# top.net
KiCad netlist of a schematic drawn in EAGLE
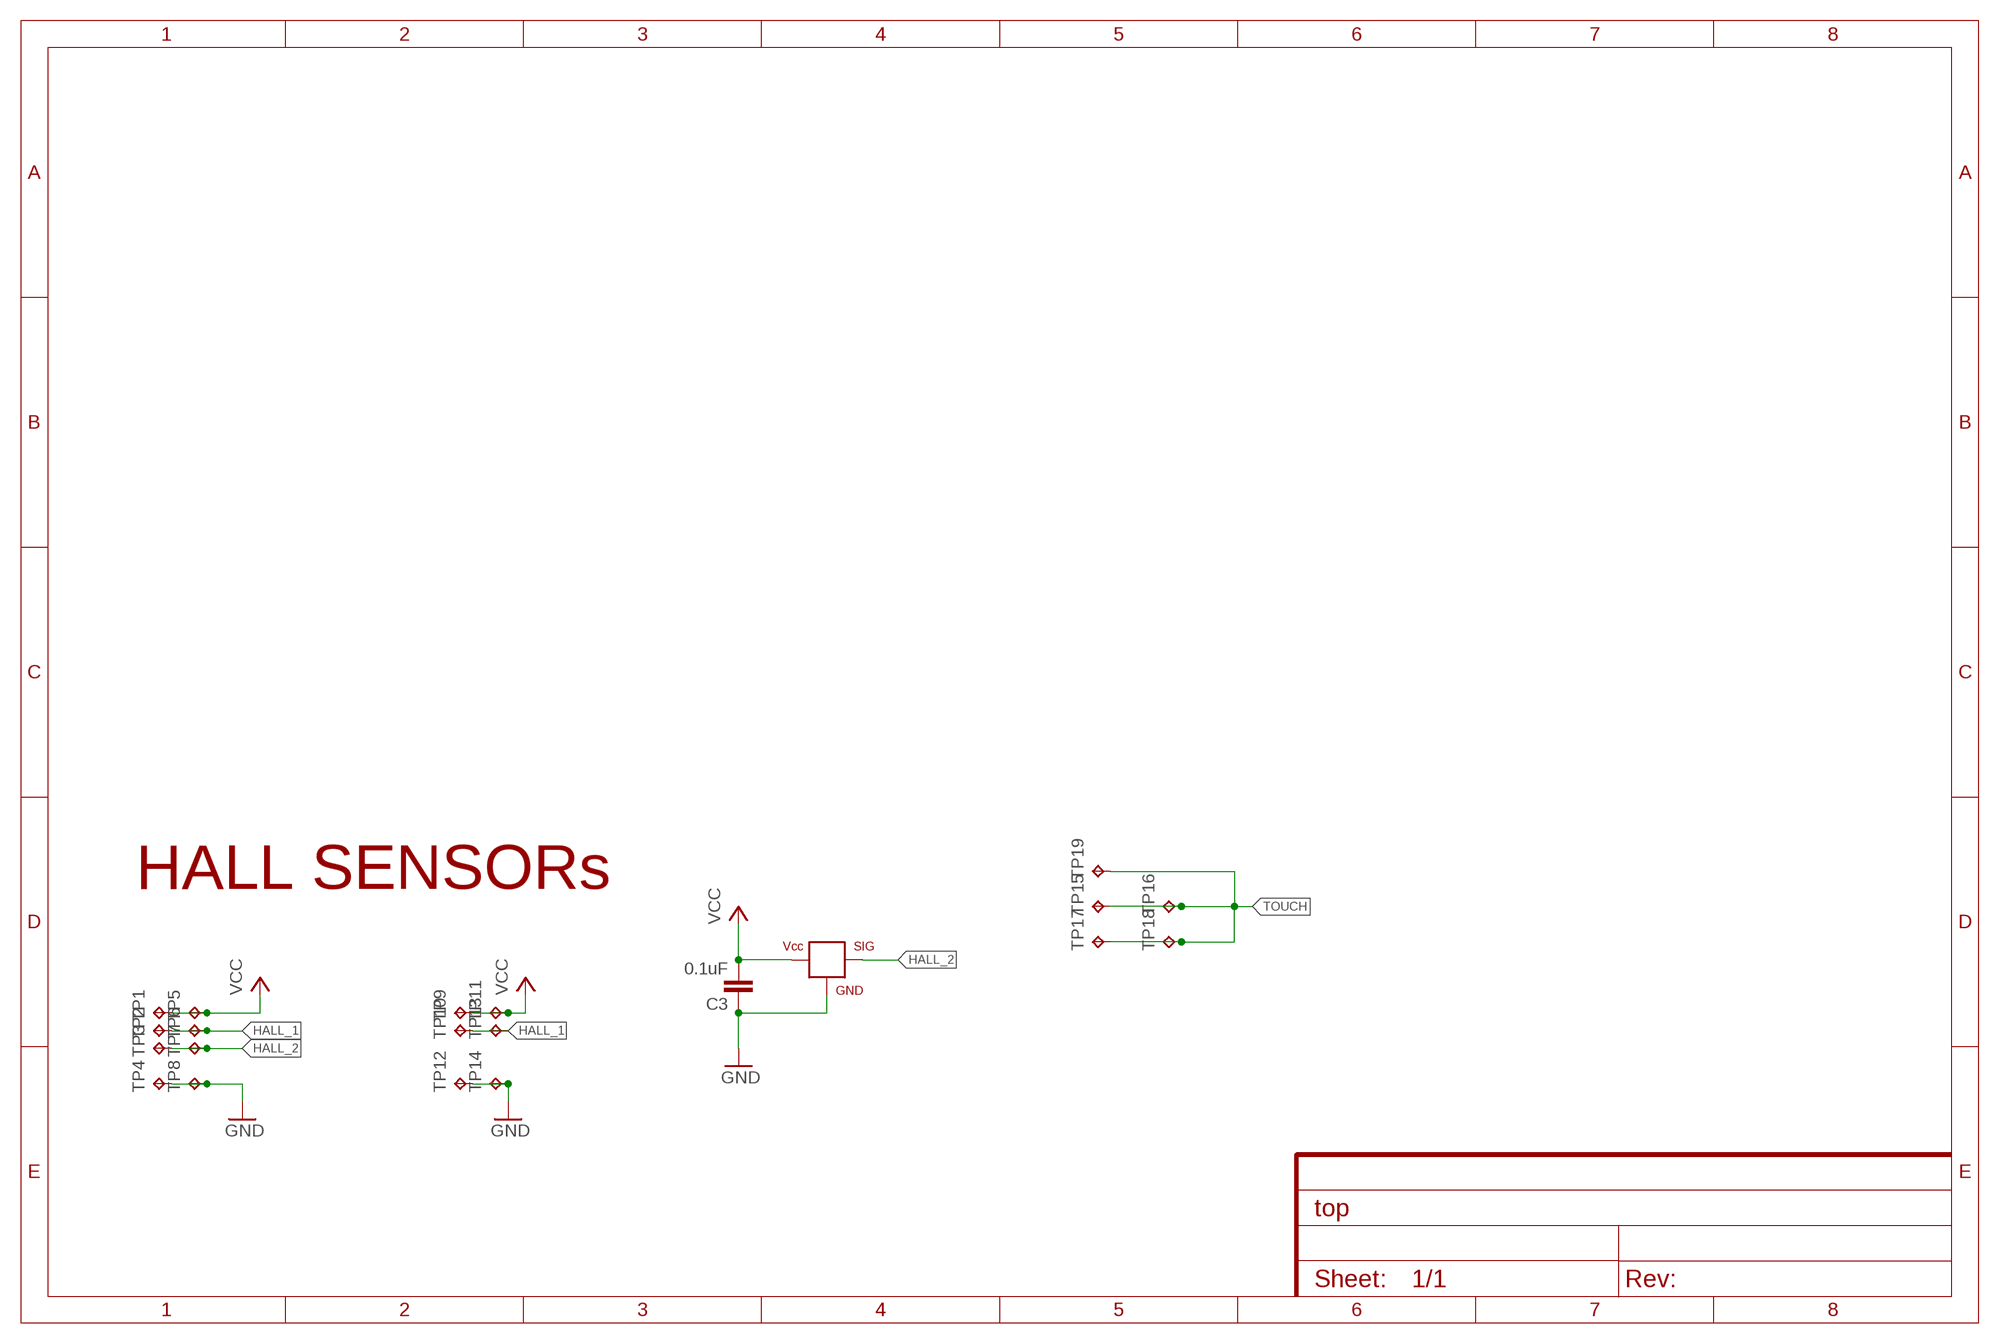
[diagram p0: schematic, sheet 1]

(export (version "E")
  (design (tool "Eeschema 10.0.6"))
  (components
    (comp (ref "C3")
      (value "0.1uF")
      (footprint "eagle-import:0603-CAP")
      (libsource (lib "eagle-import") (part "CAP0603-CAP"))
    )
    (comp (ref "HALL")
      (value "HALLEFFECT-A1326")
      (footprint "eagle-import:SOT23-3")
      (libsource (lib "eagle-import") (part "HALLEFFECT-A1326"))
    )
    (comp (ref "TP1")
      (value "TPTP10SQ")
      (footprint "eagle-import:TP10SQ")
      (libsource (lib "eagle-import") (part "TPTP10SQ"))
    )
    (comp (ref "TP2")
      (value "TPTP10SQ")
      (footprint "eagle-import:TP10SQ")
      (libsource (lib "eagle-import") (part "TPTP10SQ"))
    )
    (comp (ref "TP3")
      (value "TPTP10SQ")
      (footprint "eagle-import:TP10SQ")
      (libsource (lib "eagle-import") (part "TPTP10SQ"))
    )
    (comp (ref "TP4")
      (value "TPTP10SQ")
      (footprint "eagle-import:TP10SQ")
      (libsource (lib "eagle-import") (part "TPTP10SQ"))
    )
    (comp (ref "TP5")
      (value "TPTP10SQ")
      (footprint "eagle-import:TP10SQ")
      (libsource (lib "eagle-import") (part "TPTP10SQ"))
    )
    (comp (ref "TP6")
      (value "TPTP10SQ")
      (footprint "eagle-import:TP10SQ")
      (libsource (lib "eagle-import") (part "TPTP10SQ"))
    )
    (comp (ref "TP7")
      (value "TPTP10SQ")
      (footprint "eagle-import:TP10SQ")
      (libsource (lib "eagle-import") (part "TPTP10SQ"))
    )
    (comp (ref "TP8")
      (value "TPTP10SQ")
      (footprint "eagle-import:TP10SQ")
      (libsource (lib "eagle-import") (part "TPTP10SQ"))
    )
    (comp (ref "TP9")
      (value "TPTP10SQ")
      (footprint "eagle-import:TP10SQ")
      (libsource (lib "eagle-import") (part "TPTP10SQ"))
    )
    (comp (ref "TP10")
      (value "TPTP10SQ")
      (footprint "eagle-import:TP10SQ")
      (libsource (lib "eagle-import") (part "TPTP10SQ"))
    )
    (comp (ref "TP11")
      (value "TPTP10SQ")
      (footprint "eagle-import:TP10SQ")
      (libsource (lib "eagle-import") (part "TPTP10SQ"))
    )
    (comp (ref "TP12")
      (value "TPTP10SQ")
      (footprint "eagle-import:TP10SQ")
      (libsource (lib "eagle-import") (part "TPTP10SQ"))
    )
    (comp (ref "TP13")
      (value "TPTP10SQ")
      (footprint "eagle-import:TP10SQ")
      (libsource (lib "eagle-import") (part "TPTP10SQ"))
    )
    (comp (ref "TP14")
      (value "TPTP10SQ")
      (footprint "eagle-import:TP10SQ")
      (libsource (lib "eagle-import") (part "TPTP10SQ"))
    )
    (comp (ref "TP15")
      (value "TPTP10SQ")
      (footprint "eagle-import:TP10SQ")
      (libsource (lib "eagle-import") (part "TPTP10SQ"))
    )
    (comp (ref "TP16")
      (value "TPTP10SQ")
      (footprint "eagle-import:TP10SQ")
      (libsource (lib "eagle-import") (part "TPTP10SQ"))
    )
    (comp (ref "TP17")
      (value "TPTP10SQ")
      (footprint "eagle-import:TP10SQ")
      (libsource (lib "eagle-import") (part "TPTP10SQ"))
    )
    (comp (ref "TP18")
      (value "TPTP10SQ")
      (footprint "eagle-import:TP10SQ")
      (libsource (lib "eagle-import") (part "TPTP10SQ"))
    )
    (comp (ref "TP19")
      (value "TPTP10SQ")
      (footprint "eagle-import:TP10SQ")
      (libsource (lib "eagle-import") (part "TPTP10SQ"))
    )
  )
  (nets
    (net (code "1") (name "GND") (class "Default")
      (node (ref "C3") (pin "1") (pinfunction "1_1") (pintype "passive"))
      (node (ref "HALL") (pin "3") (pinfunction "GND_3") (pintype "bidirectional"))
      (node (ref "TP12") (pin "TP") (pinfunction "TP_TP") (pintype "input"))
      (node (ref "TP14") (pin "TP") (pinfunction "TP_TP") (pintype "input"))
      (node (ref "TP4") (pin "TP") (pinfunction "TP_TP") (pintype "input"))
      (node (ref "TP8") (pin "TP") (pinfunction "TP_TP") (pintype "input"))
    )
    (net (code "2") (name "HALL_1") (class "Default")
      (node (ref "TP10") (pin "TP") (pinfunction "TP_TP") (pintype "input"))
      (node (ref "TP13") (pin "TP") (pinfunction "TP_TP") (pintype "input"))
      (node (ref "TP2") (pin "TP") (pinfunction "TP_TP") (pintype "input"))
      (node (ref "TP6") (pin "TP") (pinfunction "TP_TP") (pintype "input"))
    )
    (net (code "3") (name "HALL_2") (class "Default")
      (node (ref "HALL") (pin "2") (pinfunction "SIG_2") (pintype "bidirectional"))
      (node (ref "TP3") (pin "TP") (pinfunction "TP_TP") (pintype "input"))
      (node (ref "TP7") (pin "TP") (pinfunction "TP_TP") (pintype "input"))
    )
    (net (code "4") (name "TOUCH") (class "Default")
      (node (ref "TP15") (pin "TP") (pinfunction "TP_TP") (pintype "input"))
      (node (ref "TP16") (pin "TP") (pinfunction "TP_TP") (pintype "input"))
      (node (ref "TP17") (pin "TP") (pinfunction "TP_TP") (pintype "input"))
      (node (ref "TP18") (pin "TP") (pinfunction "TP_TP") (pintype "input"))
      (node (ref "TP19") (pin "TP") (pinfunction "TP_TP") (pintype "input"))
    )
    (net (code "5") (name "VCC") (class "Default")
      (node (ref "C3") (pin "2") (pinfunction "2_2") (pintype "passive"))
      (node (ref "HALL") (pin "1") (pinfunction "VCC_1") (pintype "bidirectional"))
      (node (ref "TP1") (pin "TP") (pinfunction "TP_TP") (pintype "input"))
      (node (ref "TP11") (pin "TP") (pinfunction "TP_TP") (pintype "input"))
      (node (ref "TP5") (pin "TP") (pinfunction "TP_TP") (pintype "input"))
      (node (ref "TP9") (pin "TP") (pinfunction "TP_TP") (pintype "input"))
    )
  )
)
